# 1_4.net
KiCad netlist of a schematic drawn in Altium Designer
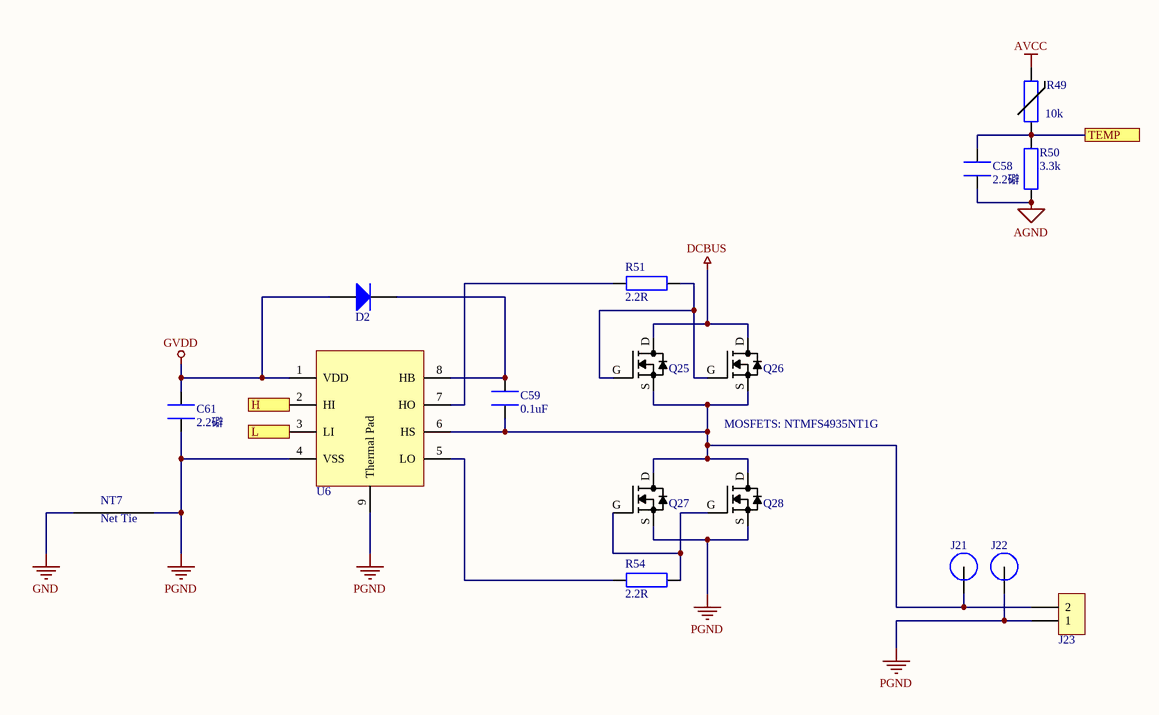
[diagram p0: 1.4.SchDoc]

(export (version "E")
  (design (tool "Eeschema 10.0.6"))
  (components
    (comp (ref "C58")
      (value "2.2礔")
      (footprint "CAPC1608X09L")
      (description "CAP CER 2.2UF 16V X5R 0603")
      (fields
        (field (name "MANUFACTURER") "Murata Electronics North America")
        (field (name "MANUFACTURER PART NUMBER") "GRM188R61C225KE15D")
      )
      (libsource (lib "CustomComponents") (part "GRM188R61C225KE15D"))
    )
    (comp (ref "C59")
      (value "0.1uF")
      (footprint "CAPC1608X09L")
      (description "CAP CER 0.1UF 50V X7R 0603")
      (fields
        (field (name "MANUFACTURER") "Murata Electronics North America")
        (field (name "MANUFACTURER PART NUMBER") "GRM188R71H104KA93D")
      )
      (libsource (lib "CustomComponents") (part "GRM188R71H104KA93D"))
    )
    (comp (ref "C61")
      (value "2.2礔")
      (footprint "CAPC1608X09L")
      (description "CAP CER 2.2UF 16V X5R 0603")
      (fields
        (field (name "MANUFACTURER") "Murata Electronics North America")
        (field (name "MANUFACTURER PART NUMBER") "GRM188R61C225KE15D")
      )
      (libsource (lib "CustomComponents") (part "GRM188R61C225KE15D"))
    )
    (comp (ref "D2")
      (value "~")
      (footprint "DIOM2717X10N")
      (description "Rectifier Diode, Single, 40 V, 1 A, SOD-123FL, 2, 550 mV")
      (libsource (lib "CustomComponents") (part "MBR140SFT1G"))
    )
    (comp (ref "J21")
      (value "~")
      (footprint "M3 Spade Hole")
      (description "M3 Spade Terminal")
      (libsource (lib "CustomComponents") (part "M3 Spade Terminal"))
    )
    (comp (ref "J22")
      (value "~")
      (footprint "M3 Spade Hole")
      (description "M3 Spade Terminal")
      (libsource (lib "CustomComponents") (part "M3 Spade Terminal"))
    )
    (comp (ref "J23")
      (value "1868076")
      (footprint "1868076")
      (description "CONN TERM BLOCK 2POS 7.62MM")
      (fields (field (name "MANUFACTURER") "Phoenix Contact") (field (name "VOLTAGE") "300V"))
      (libsource (lib "CustomComponents") (part "1868076"))
    )
    (comp (ref "NT7")
      (value "0.25mm")
      (footprint "NetTie_0.25mm")
      (libsource (lib "CustomComponents") (part "NetTie_0.25mm"))
    )
    (comp (ref "Q25")
      (value "FILL_FOOTPRINT")
      (footprint "SO8FL_FILL")
      (description "MOSFET N-CH 30V 13A SO8FL")
      (fields
        (field (name "MANUFACTURER") "ON Semiconductor")
        (field (name "MANUFACTURER PART NUMBER") "NTMFS4935NT1G")
      )
      (libsource (lib "CustomComponents") (part "NTMFS4935NT1G"))
    )
    (comp (ref "Q26")
      (value "~")
      (footprint "SO8FL")
      (description "MOSFET N-CH 30V 13A SO8FL")
      (fields
        (field (name "MANUFACTURER") "ON Semiconductor")
        (field (name "MANUFACTURER PART NUMBER") "NTMFS4935NT1G")
      )
      (libsource (lib "CustomComponents") (part "NTMFS4935NT1G"))
    )
    (comp (ref "Q27")
      (value "~")
      (footprint "SO8FL")
      (description "MOSFET N-CH 30V 13A SO8FL")
      (fields
        (field (name "MANUFACTURER") "ON Semiconductor")
        (field (name "MANUFACTURER PART NUMBER") "NTMFS4935NT1G")
      )
      (libsource (lib "CustomComponents") (part "NTMFS4935NT1G"))
    )
    (comp (ref "Q28")
      (value "~")
      (footprint "SO8FL")
      (description "MOSFET N-CH 30V 13A SO8FL")
      (fields
        (field (name "MANUFACTURER") "ON Semiconductor")
        (field (name "MANUFACTURER PART NUMBER") "NTMFS4935NT1G")
      )
      (libsource (lib "CustomComponents") (part "NTMFS4935NT1G"))
    )
    (comp (ref "R49")
      (value "10k")
      (footprint "RESC1005X40N")
      (description "THERMISTOR 10K OHM NTC 0402 SMD")
      (libsource (lib "CustomComponents") (part "NCP15XH103F03RC"))
    )
    (comp (ref "R50")
      (value "3.3k")
      (footprint "RESC1608X55N")
      (description "RES SMD 3.3K OHM 1% 1/10W 0603")
      (fields
        (field (name "MANUFACTURER") "Yageo")
        (field (name "MANUFACTURER PART NUMBER") "RC0603FR-073K3L")
      )
      (libsource (lib "CustomComponents") (part "RC0603FR-073K3L"))
    )
    (comp (ref "R51")
      (value "2.2R")
      (footprint "RESC1608X55N")
      (description "RES SMD 2.2 OHM 1% 1/10W 0603")
      (fields
        (field (name "MANUFACTURER") "Yageo")
        (field (name "MANUFACTURER PART NUMBER") "RC0603FR-072R2L")
      )
      (libsource (lib "CustomComponents") (part "RC0603FR-072R2L"))
    )
    (comp (ref "R54")
      (value "2.2R")
      (footprint "RESC1608X55N")
      (description "RES SMD 2.2 OHM 1% 1/10W 0603")
      (fields
        (field (name "MANUFACTURER") "Yageo")
        (field (name "MANUFACTURER PART NUMBER") "RC0603FR-072R2L")
      )
      (libsource (lib "CustomComponents") (part "RC0603FR-072R2L"))
    )
    (comp (ref "U6")
      (value "~")
      (footprint "SON80P400X80_HS-9N")
      (description "DRIVER, MOSFET, HALF BRIDGE, WSON-8, 1A")
      (libsource (lib "CustomComponents") (part "LM5109BSD/NOPB"))
    )
  )
  (nets
    (net (code "1") (name "/H") (class "Default")
      (node (ref "U6") (pin "2") (pinfunction "HI_2") (pintype "passive"))
    )
    (net (code "2") (name "/L") (class "Default")
      (node (ref "U6") (pin "3") (pinfunction "LI_3") (pintype "passive"))
    )
    (net (code "3") (name "/TEMP") (class "Default")
      (node (ref "C58") (pin "2") (pinfunction "2_2") (pintype "passive"))
      (node (ref "R49") (pin "1") (pinfunction "0_1") (pintype "passive"))
      (node (ref "R50") (pin "1") (pinfunction "0_1") (pintype "passive"))
    )
    (net (code "4") (name "AGND") (class "Default")
      (node (ref "C58") (pin "1") (pinfunction "1_1") (pintype "passive"))
      (node (ref "R50") (pin "2") (pinfunction "0_2") (pintype "passive"))
    )
    (net (code "5") (name "AVCC") (class "Default")
      (node (ref "R49") (pin "2") (pinfunction "0_2") (pintype "passive"))
    )
    (net (code "6") (name "DCBUS") (class "Default")
      (node (ref "Q25") (pin "D") (pinfunction "D_D") (pintype "passive"))
      (node (ref "Q26") (pin "D") (pinfunction "D_D") (pintype "passive"))
    )
    (net (code "7") (name "GND") (class "Default") (node (ref "NT7") (pin "1") (pintype "passive")))
    (net (code "8") (name "GVDD") (class "Default")
      (node (ref "C61") (pin "2") (pinfunction "2_2") (pintype "passive"))
      (node (ref "D2") (pin "A") (pinfunction "A_A") (pintype "passive"))
      (node (ref "U6") (pin "1") (pinfunction "VDD_1") (pintype "passive"))
    )
    (net (code "9") (name "Net-(Q25-PadG)") (class "Default")
      (node (ref "Q25") (pin "G") (pinfunction "G_G") (pintype "passive"))
      (node (ref "Q26") (pin "G") (pinfunction "G_G") (pintype "passive"))
      (node (ref "R51") (pin "2") (pinfunction "0_2") (pintype "passive"))
    )
    (net (code "10") (name "Net-(Q27-PadG)") (class "Default")
      (node (ref "Q27") (pin "G") (pinfunction "G_G") (pintype "passive"))
      (node (ref "Q28") (pin "G") (pinfunction "G_G") (pintype "passive"))
      (node (ref "R54") (pin "2") (pinfunction "0_2") (pintype "passive"))
    )
    (net (code "11") (name "Net-(U6-HB)") (class "Default")
      (node (ref "C59") (pin "1") (pinfunction "1_1") (pintype "passive"))
      (node (ref "D2") (pin "K") (pinfunction "K_K") (pintype "passive"))
      (node (ref "U6") (pin "8") (pinfunction "HB_8") (pintype "passive"))
    )
    (net (code "12") (name "Net-(U6-HO)") (class "Default")
      (node (ref "R51") (pin "1") (pinfunction "0_1") (pintype "passive"))
      (node (ref "U6") (pin "7") (pinfunction "HO_7") (pintype "passive"))
    )
    (net (code "13") (name "Net-(U6-HS)") (class "Default")
      (node (ref "C59") (pin "2") (pinfunction "2_2") (pintype "passive"))
      (node (ref "J21") (pin "1") (pinfunction "1_1") (pintype "passive"))
      (node (ref "J23") (pin "2") (pinfunction "2_2") (pintype "passive"))
      (node (ref "Q25") (pin "S") (pinfunction "S_S") (pintype "passive"))
      (node (ref "Q26") (pin "S") (pinfunction "S_S") (pintype "passive"))
      (node (ref "Q27") (pin "D") (pinfunction "D_D") (pintype "passive"))
      (node (ref "Q28") (pin "D") (pinfunction "D_D") (pintype "passive"))
      (node (ref "U6") (pin "6") (pinfunction "HS_6") (pintype "passive"))
    )
    (net (code "14") (name "Net-(U6-LO)") (class "Default")
      (node (ref "R54") (pin "1") (pinfunction "0_1") (pintype "passive"))
      (node (ref "U6") (pin "5") (pinfunction "LO_5") (pintype "passive"))
    )
    (net (code "15") (name "PGND") (class "Default")
      (node (ref "C61") (pin "1") (pinfunction "1_1") (pintype "passive"))
      (node (ref "J22") (pin "1") (pinfunction "1_1") (pintype "passive"))
      (node (ref "J23") (pin "1") (pinfunction "1_1") (pintype "passive"))
      (node (ref "NT7") (pin "2") (pintype "passive"))
      (node (ref "Q27") (pin "S") (pinfunction "S_S") (pintype "passive"))
      (node (ref "Q28") (pin "S") (pinfunction "S_S") (pintype "passive"))
      (node (ref "U6") (pin "4") (pinfunction "VSS_4") (pintype "passive"))
      (node (ref "U6") (pin "9") (pinfunction "Thermal_Pad_9") (pintype "passive"))
    )
  )
)
